# Lazy_Frog.net
KiCad netlist of a schematic drawn in EAGLE
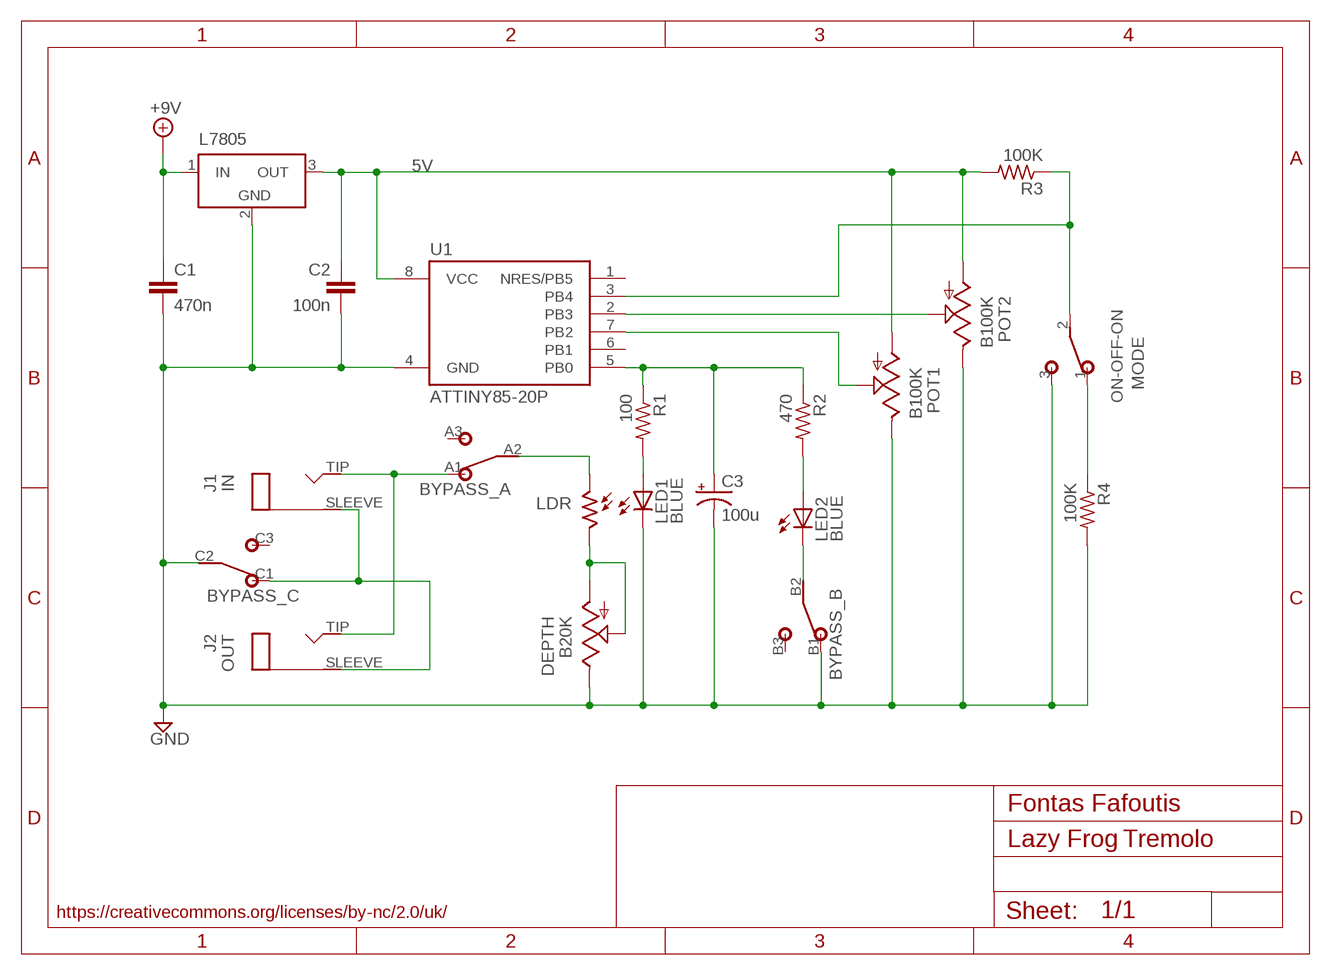
[diagram p0: schematic, sheet 1]

(export (version "E")
  (design (tool "Eeschema 10.0.6"))
  (components
    (comp (ref "BYPASS_")
      (value "3PDT")
      (footprint "eagle-import:3PDT")
      (libsource (lib "eagle-import") (part "3PDT"))
    )
    (comp (ref "C1")
      (value "470n")
      (footprint "eagle-import:072X035")
      (libsource (lib "eagle-import") (part "072X0352"))
    )
    (comp (ref "C2")
      (value "100n")
      (footprint "eagle-import:072X035")
      (libsource (lib "eagle-import") (part "072X0352"))
    )
    (comp (ref "C3")
      (value "100u")
      (footprint "eagle-import:063_025")
      (libsource (lib "eagle-import") (part "0631"))
    )
    (comp (ref "DEPTH")
      (value "B20K")
      (footprint "eagle-import:3223G")
      (libsource (lib "eagle-import") (part "TRIM_US-3223G"))
    )
    (comp (ref "J1")
      (value "IN")
      (footprint "eagle-import:MONO_JACK")
      (libsource (lib "eagle-import") (part "MONO"))
    )
    (comp (ref "J2")
      (value "OUT")
      (footprint "eagle-import:MONO_JACK")
      (libsource (lib "eagle-import") (part "MONO"))
    )
    (comp (ref "L7805")
      (value "LT1129CST5")
      (footprint "eagle-import:SOT223")
      (fields (field (name "MPN") "LT1129CST-5#PBF"))
      (libsource (lib "eagle-import") (part "LT1129CST5"))
    )
    (comp (ref "LDR")
      (value "PHOTOCELLD11")
      (footprint "eagle-import:D11XX_H")
      (libsource (lib "eagle-import") (part "PHOTOCELLD11"))
    )
    (comp (ref "LED1")
      (value "BLUE")
      (footprint "eagle-import:SMARTLED-TTW")
      (libsource (lib "eagle-import") (part "LED"))
    )
    (comp (ref "LED2")
      (value "BLUE")
      (footprint "eagle-import:SMARTLED-TTW")
      (libsource (lib "eagle-import") (part "LED"))
    )
    (comp (ref "MODE")
      (value "ON-OFF-ON")
      (footprint "eagle-import:SPDT")
      (libsource (lib "eagle-import") (part "SPDTPADS"))
    )
    (comp (ref "POT1")
      (value "B100K")
      (footprint "eagle-import:3223G")
      (libsource (lib "eagle-import") (part "TRIM_US-3223G"))
    )
    (comp (ref "POT2")
      (value "B100K")
      (footprint "eagle-import:3223G")
      (libsource (lib "eagle-import") (part "TRIM_US-3223G"))
    )
    (comp (ref "R1")
      (value "100")
      (footprint "eagle-import:0204_7")
      (libsource (lib "eagle-import") (part "R-US_0204/7"))
    )
    (comp (ref "R2")
      (value "470")
      (footprint "eagle-import:0204_7")
      (libsource (lib "eagle-import") (part "R-US_0204/7"))
    )
    (comp (ref "R3")
      (value "100K")
      (footprint "eagle-import:0204_7")
      (libsource (lib "eagle-import") (part "R-US_0204/7"))
    )
    (comp (ref "R4")
      (value "100K")
      (footprint "eagle-import:0204_7")
      (libsource (lib "eagle-import") (part "R-US_0204/7"))
    )
    (comp (ref "U1")
      (value "ATTINY85-20P")
      (footprint "eagle-import:PDIP08_300MIL")
      (libsource (lib "eagle-import") (part "ATTINY85P-20"))
    )
  )
  (nets
    (net (code "1") (name "+9V") (class "Default")
      (node (ref "C1") (pin "1") (pinfunction "1_1") (pintype "passive"))
      (node (ref "L7805") (pin "1") (pinfunction "IN_1") (pintype "input"))
    )
    (net (code "2") (name "/5V") (class "Default")
      (node (ref "C2") (pin "1") (pinfunction "1_1") (pintype "passive"))
      (node (ref "L7805") (pin "3") (pinfunction "OUT_3") (pintype "output"))
      (node (ref "POT1") (pin "1") (pinfunction "A_1") (pintype "passive"))
      (node (ref "POT2") (pin "1") (pinfunction "A_1") (pintype "passive"))
      (node (ref "R3") (pin "2") (pinfunction "2_2") (pintype "passive"))
      (node (ref "U1") (pin "8") (pinfunction "VCC_8") (pintype "power_in"))
    )
    (net (code "3") (name "GND") (class "Default")
      (node (ref "BYPASS_") (pin "B1") (pinfunction "1_B1") (pintype "passive"))
      (node (ref "BYPASS_") (pin "C2") (pinfunction "2_C2") (pintype "passive"))
      (node (ref "C1") (pin "2") (pinfunction "2_2") (pintype "passive"))
      (node (ref "C2") (pin "2") (pinfunction "2_2") (pintype "passive"))
      (node (ref "C3") (pin "-") (pinfunction "-_-") (pintype "passive"))
      (node (ref "DEPTH") (pin "3") (pinfunction "E_3") (pintype "passive"))
      (node (ref "L7805") (pin "2") (pinfunction "GND_2") (pintype "power_in"))
      (node (ref "LED1") (pin "C@1") (pinfunction "C_C@1") (pintype "passive"))
      (node (ref "MODE") (pin "3") (pinfunction "S_3") (pintype "passive"))
      (node (ref "POT1") (pin "3") (pinfunction "E_3") (pintype "passive"))
      (node (ref "POT2") (pin "3") (pinfunction "E_3") (pintype "passive"))
      (node (ref "R4") (pin "2") (pinfunction "2_2") (pintype "passive"))
      (node (ref "U1") (pin "4") (pinfunction "GND_4") (pintype "power_in"))
    )
    (net (code "4") (name "Net-(BYPASS_A-1)") (class "Default")
      (node (ref "BYPASS_") (pin "A1") (pinfunction "1_A1") (pintype "passive"))
      (node (ref "J1") (pin "TIP") (pinfunction "TIP_TIP") (pintype "passive"))
      (node (ref "J2") (pin "TIP") (pinfunction "TIP_TIP") (pintype "passive"))
    )
    (net (code "5") (name "Net-(BYPASS_A-2)") (class "Default")
      (node (ref "BYPASS_") (pin "A2") (pinfunction "2_A2") (pintype "passive"))
      (node (ref "LDR") (pin "1") (pinfunction "1_1") (pintype "passive"))
    )
    (net (code "6") (name "Net-(BYPASS_B-2)") (class "Default")
      (node (ref "BYPASS_") (pin "B2") (pinfunction "2_B2") (pintype "passive"))
      (node (ref "LED2") (pin "C@1") (pinfunction "C_C@1") (pintype "passive"))
    )
    (net (code "7") (name "Net-(BYPASS_C-1)") (class "Default")
      (node (ref "BYPASS_") (pin "C1") (pinfunction "1_C1") (pintype "passive"))
      (node (ref "J1") (pin "SLEEVE") (pinfunction "SLEEVE_SLEEVE") (pintype "passive"))
      (node (ref "J2") (pin "SLEEVE") (pinfunction "SLEEVE_SLEEVE") (pintype "passive"))
    )
    (net (code "8") (name "Net-(DEPTH-A)") (class "Default")
      (node (ref "DEPTH") (pin "1") (pinfunction "A_1") (pintype "passive"))
      (node (ref "DEPTH") (pin "2") (pinfunction "S_2") (pintype "passive"))
      (node (ref "LDR") (pin "2") (pinfunction "2_2") (pintype "passive"))
    )
    (net (code "9") (name "Net-(LED1-A)") (class "Default")
      (node (ref "LED1") (pin "A@1") (pinfunction "A_A@1") (pintype "passive"))
      (node (ref "R1") (pin "2") (pinfunction "2_2") (pintype "passive"))
    )
    (net (code "10") (name "Net-(LED2-A)") (class "Default")
      (node (ref "LED2") (pin "A@1") (pinfunction "A_A@1") (pintype "passive"))
      (node (ref "R2") (pin "2") (pinfunction "2_2") (pintype "passive"))
    )
    (net (code "11") (name "Net-(MODE-O)") (class "Default")
      (node (ref "MODE") (pin "1") (pinfunction "O_1") (pintype "passive"))
      (node (ref "R4") (pin "1") (pinfunction "1_1") (pintype "passive"))
    )
    (net (code "12") (name "Net-(MODE-P)") (class "Default")
      (node (ref "MODE") (pin "2") (pinfunction "P_2") (pintype "passive"))
      (node (ref "R3") (pin "1") (pinfunction "1_1") (pintype "passive"))
      (node (ref "U1") (pin "3") (pinfunction "PB4_3") (pintype "bidirectional"))
    )
    (net (code "13") (name "Net-(POT1-S)") (class "Default")
      (node (ref "POT1") (pin "2") (pinfunction "S_2") (pintype "passive"))
      (node (ref "U1") (pin "7") (pinfunction "PB2_7") (pintype "bidirectional"))
    )
    (net (code "14") (name "Net-(POT2-S)") (class "Default")
      (node (ref "POT2") (pin "2") (pinfunction "S_2") (pintype "passive"))
      (node (ref "U1") (pin "2") (pinfunction "PB3_2") (pintype "bidirectional"))
    )
    (net (code "15") (name "Net-(U1-PB0)") (class "Default")
      (node (ref "C3") (pin "+") (pinfunction "+_+") (pintype "passive"))
      (node (ref "R1") (pin "1") (pinfunction "1_1") (pintype "passive"))
      (node (ref "R2") (pin "1") (pinfunction "1_1") (pintype "passive"))
      (node (ref "U1") (pin "5") (pinfunction "PB0_5") (pintype "bidirectional"))
    )
    (net (code "16") (name "unconnected-(BYPASS_A-3-PadA3)") (class "Default")
      (node (ref "BYPASS_") (pin "A3") (pinfunction "3_A3") (pintype "passive"))
    )
    (net (code "17") (name "unconnected-(BYPASS_B-3-PadB3)") (class "Default")
      (node (ref "BYPASS_") (pin "B3") (pinfunction "3_B3") (pintype "passive"))
    )
    (net (code "18") (name "unconnected-(BYPASS_C-3-PadC3)") (class "Default")
      (node (ref "BYPASS_") (pin "C3") (pinfunction "3_C3") (pintype "passive"))
    )
    (net (code "19") (name "unconnected-(U1-NRES{slash}PB5-Pad1)") (class "Default")
      (node (ref "U1") (pin "1") (pinfunction "NRES/PB5_1") (pintype "bidirectional"))
    )
    (net (code "20") (name "unconnected-(U1-PB1-Pad6)") (class "Default")
      (node (ref "U1") (pin "6") (pinfunction "PB1_6") (pintype "bidirectional"))
    )
  )
)
